# Peripheral.net
KiCad netlist of a schematic drawn in Altium Designer
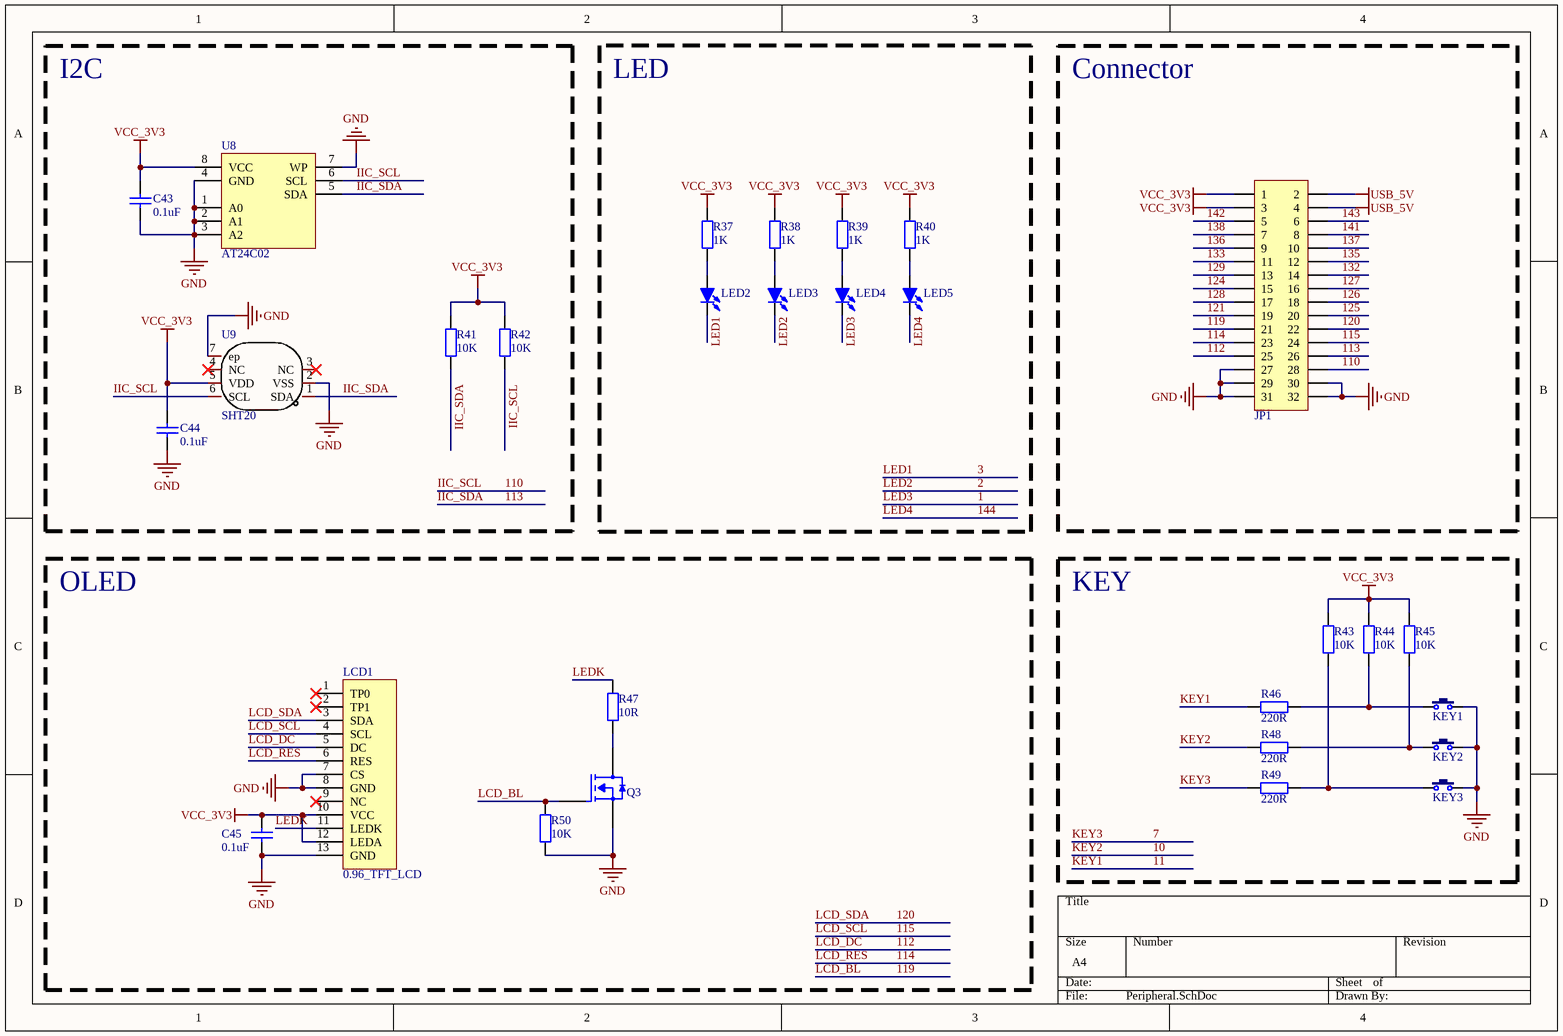
[diagram p0: Peripheral.SchDoc]

(export (version "E")
  (design (tool "Eeschema 10.0.6"))
  (components
    (comp (ref "C43")
      (value "0.1uF")
      (footprint "0402_C")
      (description "贴片电容")
      (libsource (lib "My_Devices") (part "0402_C"))
    )
    (comp (ref "C44")
      (value "0.1uF")
      (footprint "0402_C")
      (description "贴片电容")
      (libsource (lib "My_Devices") (part "0402_C"))
    )
    (comp (ref "C45")
      (value "0.1uF")
      (footprint "0402_C")
      (description "贴片电容")
      (libsource (lib "My_Devices") (part "0402_C"))
    )
    (comp (ref "JP1")
      (value "Header 2X11")
      (footprint "HDR2.54-LI-2x16P")
      (description "16*2P接插件")
      (fields (field (name "版权归属") "源创客"))
      (libsource (lib "My_Devices") (part "Header 16X2_2.54"))
    )
    (comp (ref "KEY1")
      (value "3x6x5")
      (footprint "SW")
      (description "3x6轻触开关")
      (fields (field (name "版权归属") "源创客"))
      (libsource (lib "My_Devices") (part "TSW 3x6"))
    )
    (comp (ref "KEY2")
      (value "3x6x5")
      (footprint "SW")
      (description "3x6轻触开关")
      (fields (field (name "版权归属") "源创客"))
      (libsource (lib "My_Devices") (part "TSW 3x6"))
    )
    (comp (ref "KEY3")
      (value "3x6x5")
      (footprint "SW")
      (description "3x6轻触开关")
      (fields (field (name "版权归属") "源创客"))
      (libsource (lib "My_Devices") (part "TSW 3x6"))
    )
    (comp (ref "LCD1")
      (value "0.96_TFT_LCD")
      (footprint "0.78_TFT_LCD")
      (libsource (lib "Schlib1") (part "0.96_TFT_LCD"))
    )
    (comp (ref "LED2")
      (value "红色")
      (footprint "LED 0603B")
      (description "贴片LED")
      (fields (field (name "版权归属") "源创客"))
      (libsource (lib "My_Devices") (part "0603_LED_B"))
    )
    (comp (ref "LED3")
      (value "红色")
      (footprint "LED 0603G")
      (description "贴片LED")
      (fields (field (name "版权归属") "源创客"))
      (libsource (lib "My_Devices") (part "0603_LED_G"))
    )
    (comp (ref "LED4")
      (value "红色")
      (footprint "LED 0603R")
      (description "贴片LED")
      (fields (field (name "版权归属") "源创客"))
      (libsource (lib "My_Devices") (part "0603_LED_R"))
    )
    (comp (ref "LED5")
      (value "红色")
      (footprint "LED 0603R")
      (description "贴片LED")
      (fields (field (name "版权归属") "源创客"))
      (libsource (lib "My_Devices") (part "0603_LED_R"))
    )
    (comp (ref "Q3")
      (value "AO3400A")
      (footprint "SOT23-3")
      (description "N-MOS")
      (libsource (lib "Schlib1") (part "AO3400A"))
    )
    (comp (ref "R37")
      (value "1K")
      (footprint "0402_R")
      (description "贴片电阻")
      (libsource (lib "My_Devices") (part "0402_R"))
    )
    (comp (ref "R38")
      (value "1K")
      (footprint "0402_R")
      (description "贴片电阻")
      (libsource (lib "My_Devices") (part "0402_R"))
    )
    (comp (ref "R39")
      (value "1K")
      (footprint "0402_R")
      (description "贴片电阻")
      (libsource (lib "My_Devices") (part "0402_R"))
    )
    (comp (ref "R40")
      (value "1K")
      (footprint "0402_R")
      (description "贴片电阻")
      (libsource (lib "My_Devices") (part "0402_R"))
    )
    (comp (ref "R41")
      (value "10K")
      (footprint "0402_R")
      (description "贴片电阻")
      (libsource (lib "") (part "0402_R_1"))
    )
    (comp (ref "R42")
      (value "10K")
      (footprint "0402_R")
      (description "贴片电阻")
      (libsource (lib "") (part "0402_R_1"))
    )
    (comp (ref "R43")
      (value "10K")
      (footprint "0402_R")
      (description "贴片电阻")
      (libsource (lib "") (part "0402_R_1"))
    )
    (comp (ref "R44")
      (value "10K")
      (footprint "0402_R")
      (description "贴片电阻")
      (libsource (lib "My_Devices") (part "0402_R"))
    )
    (comp (ref "R45")
      (value "10K")
      (footprint "0402_R")
      (description "贴片电阻")
      (libsource (lib "My_Devices") (part "0402_R"))
    )
    (comp (ref "R46")
      (value "220R")
      (footprint "0402_R")
      (description "贴片电阻")
      (libsource (lib "") (part "0402_R_1"))
    )
    (comp (ref "R47")
      (value "10R")
      (footprint "0402_R")
      (description "贴片电阻")
      (libsource (lib "My_Devices") (part "0402_R"))
    )
    (comp (ref "R48")
      (value "220R")
      (footprint "0402_R")
      (description "贴片电阻")
      (libsource (lib "") (part "0402_R_1"))
    )
    (comp (ref "R49")
      (value "220R")
      (footprint "0402_R")
      (description "贴片电阻")
      (libsource (lib "") (part "0402_R_1"))
    )
    (comp (ref "R50")
      (value "10K")
      (footprint "0402_R")
      (description "贴片电阻")
      (libsource (lib "My_Devices") (part "0402_R"))
    )
    (comp (ref "U8") (value "AT24C02") (footprint "SOP8_N") (libsource (lib "Schlib1") (part "AT24C02")))
    (comp (ref "U9")
      (value "SHT20")
      (footprint "DFN-6_L3.0-W3.0-P0.95-TR-EP")
      (description "I2C接口，数字式温湿度传感器，电压范围: 2.1至3.6 V")
      (fields (field (name "MANUFACTURER") "Sensirion(瑞士盛思锐)") (field (name "NAME") "SHT20"))
      (libsource (lib "Schlib1") (part "SHT20"))
    )
  )
  (nets
    (net (code "1") (name "/1") (class "Default")
      (node (ref "LED4") (pin "2") (pinfunction "K_2") (pintype "passive"))
    )
    (net (code "2") (name "/2") (class "Default")
      (node (ref "LED3") (pin "2") (pinfunction "K_2") (pintype "passive"))
    )
    (net (code "3") (name "/3") (class "Default")
      (node (ref "LED2") (pin "2") (pinfunction "K_2") (pintype "passive"))
    )
    (net (code "4") (name "/7") (class "Default")
      (node (ref "R49") (pin "2") (pinfunction "2_2") (pintype "passive"))
    )
    (net (code "5") (name "/10") (class "Default")
      (node (ref "R48") (pin "2") (pinfunction "2_2") (pintype "passive"))
    )
    (net (code "6") (name "/11") (class "Default")
      (node (ref "R46") (pin "2") (pinfunction "2_2") (pintype "passive"))
    )
    (net (code "7") (name "/110") (class "Default")
      (node (ref "JP1") (pin "28") (pinfunction "28_28") (pintype "passive"))
      (node (ref "R42") (pin "2") (pinfunction "2_2") (pintype "passive"))
      (node (ref "U8") (pin "6") (pinfunction "SCL_6") (pintype "passive"))
      (node (ref "U9") (pin "6") (pinfunction "SCL_6") (pintype "passive"))
    )
    (net (code "8") (name "/112") (class "Default")
      (node (ref "JP1") (pin "25") (pinfunction "25_25") (pintype "passive"))
      (node (ref "LCD1") (pin "5") (pinfunction "DC_5") (pintype "passive"))
    )
    (net (code "9") (name "/113") (class "Default")
      (node (ref "JP1") (pin "26") (pinfunction "26_26") (pintype "passive"))
      (node (ref "R41") (pin "2") (pinfunction "2_2") (pintype "passive"))
      (node (ref "U8") (pin "5") (pinfunction "SDA_5") (pintype "passive"))
      (node (ref "U9") (pin "1") (pinfunction "SDA_1") (pintype "passive"))
    )
    (net (code "10") (name "/114") (class "Default")
      (node (ref "JP1") (pin "23") (pinfunction "23_23") (pintype "passive"))
      (node (ref "LCD1") (pin "6") (pinfunction "RES_6") (pintype "passive"))
    )
    (net (code "11") (name "/115") (class "Default")
      (node (ref "JP1") (pin "24") (pinfunction "24_24") (pintype "passive"))
      (node (ref "LCD1") (pin "4") (pinfunction "SCL_4") (pintype "passive"))
    )
    (net (code "12") (name "/119") (class "Default")
      (node (ref "JP1") (pin "21") (pinfunction "21_21") (pintype "passive"))
      (node (ref "Q3") (pin "1") (pinfunction "G_1") (pintype "passive"))
      (node (ref "R50") (pin "2") (pinfunction "2_2") (pintype "passive"))
    )
    (net (code "13") (name "/120") (class "Default")
      (node (ref "JP1") (pin "22") (pinfunction "22_22") (pintype "passive"))
      (node (ref "LCD1") (pin "3") (pinfunction "SDA_3") (pintype "passive"))
    )
    (net (code "14") (name "/121") (class "Default")
      (node (ref "JP1") (pin "19") (pinfunction "19_19") (pintype "passive"))
    )
    (net (code "15") (name "/124") (class "Default")
      (node (ref "JP1") (pin "15") (pinfunction "15_15") (pintype "passive"))
    )
    (net (code "16") (name "/125") (class "Default")
      (node (ref "JP1") (pin "20") (pinfunction "20_20") (pintype "passive"))
    )
    (net (code "17") (name "/126") (class "Default")
      (node (ref "JP1") (pin "18") (pinfunction "18_18") (pintype "passive"))
    )
    (net (code "18") (name "/127") (class "Default")
      (node (ref "JP1") (pin "16") (pinfunction "16_16") (pintype "passive"))
    )
    (net (code "19") (name "/128") (class "Default")
      (node (ref "JP1") (pin "17") (pinfunction "17_17") (pintype "passive"))
    )
    (net (code "20") (name "/129") (class "Default")
      (node (ref "JP1") (pin "13") (pinfunction "13_13") (pintype "passive"))
    )
    (net (code "21") (name "/132") (class "Default")
      (node (ref "JP1") (pin "14") (pinfunction "14_14") (pintype "passive"))
    )
    (net (code "22") (name "/133") (class "Default")
      (node (ref "JP1") (pin "11") (pinfunction "11_11") (pintype "passive"))
    )
    (net (code "23") (name "/135") (class "Default")
      (node (ref "JP1") (pin "12") (pinfunction "12_12") (pintype "passive"))
    )
    (net (code "24") (name "/136") (class "Default")
      (node (ref "JP1") (pin "9") (pinfunction "9_9") (pintype "passive"))
    )
    (net (code "25") (name "/137") (class "Default")
      (node (ref "JP1") (pin "10") (pinfunction "10_10") (pintype "passive"))
    )
    (net (code "26") (name "/138") (class "Default")
      (node (ref "JP1") (pin "7") (pinfunction "7_7") (pintype "passive"))
    )
    (net (code "27") (name "/141") (class "Default")
      (node (ref "JP1") (pin "8") (pinfunction "8_8") (pintype "passive"))
    )
    (net (code "28") (name "/142") (class "Default")
      (node (ref "JP1") (pin "5") (pinfunction "5_5") (pintype "passive"))
    )
    (net (code "29") (name "/143") (class "Default")
      (node (ref "JP1") (pin "6") (pinfunction "6_6") (pintype "passive"))
    )
    (net (code "30") (name "/144") (class "Default")
      (node (ref "LED5") (pin "2") (pinfunction "K_2") (pintype "passive"))
    )
    (net (code "31") (name "/LEDK") (class "Default")
      (node (ref "LCD1") (pin "11") (pinfunction "LEDK_11") (pintype "passive"))
      (node (ref "R47") (pin "2") (pinfunction "2_2") (pintype "passive"))
    )
    (net (code "32") (name "GND") (class "Default")
      (node (ref "C43") (pin "1") (pinfunction "1_1") (pintype "passive"))
      (node (ref "C44") (pin "1") (pinfunction "1_1") (pintype "passive"))
      (node (ref "C45") (pin "1") (pinfunction "1_1") (pintype "passive"))
      (node (ref "JP1") (pin "27") (pinfunction "27_27") (pintype "passive"))
      (node (ref "JP1") (pin "29") (pinfunction "29_29") (pintype "passive"))
      (node (ref "JP1") (pin "30") (pinfunction "30_30") (pintype "passive"))
      (node (ref "JP1") (pin "31") (pinfunction "31_31") (pintype "passive"))
      (node (ref "JP1") (pin "32") (pinfunction "32_32") (pintype "passive"))
      (node (ref "KEY1") (pin "1") (pinfunction "1_1") (pintype "passive"))
      (node (ref "KEY2") (pin "1") (pinfunction "1_1") (pintype "passive"))
      (node (ref "KEY3") (pin "1") (pinfunction "1_1") (pintype "passive"))
      (node (ref "LCD1") (pin "13") (pinfunction "GND_13") (pintype "passive"))
      (node (ref "LCD1") (pin "7") (pinfunction "CS_7") (pintype "passive"))
      (node (ref "LCD1") (pin "8") (pinfunction "GND_8") (pintype "passive"))
      (node (ref "Q3") (pin "2") (pinfunction "S_2") (pintype "passive"))
      (node (ref "R50") (pin "1") (pinfunction "1_1") (pintype "passive"))
      (node (ref "U8") (pin "1") (pinfunction "A0_1") (pintype "passive"))
      (node (ref "U8") (pin "2") (pinfunction "A1_2") (pintype "passive"))
      (node (ref "U8") (pin "3") (pinfunction "A2_3") (pintype "passive"))
      (node (ref "U8") (pin "4") (pinfunction "GND_4") (pintype "passive"))
      (node (ref "U8") (pin "7") (pinfunction "WP_7") (pintype "passive"))
      (node (ref "U9") (pin "2") (pinfunction "VSS_2") (pintype "passive"))
      (node (ref "U9") (pin "7") (pinfunction "ep_7") (pintype "passive"))
    )
    (net (code "33") (name "Net-(KEY1-Pad2)") (class "Default")
      (node (ref "KEY1") (pin "2") (pinfunction "2_2") (pintype "passive"))
      (node (ref "R44") (pin "1") (pinfunction "1_1") (pintype "passive"))
      (node (ref "R46") (pin "1") (pinfunction "1_1") (pintype "passive"))
    )
    (net (code "34") (name "Net-(KEY2-Pad2)") (class "Default")
      (node (ref "KEY2") (pin "2") (pinfunction "2_2") (pintype "passive"))
      (node (ref "R45") (pin "1") (pinfunction "1_1") (pintype "passive"))
      (node (ref "R48") (pin "1") (pinfunction "1_1") (pintype "passive"))
    )
    (net (code "35") (name "Net-(KEY3-Pad2)") (class "Default")
      (node (ref "KEY3") (pin "2") (pinfunction "2_2") (pintype "passive"))
      (node (ref "R43") (pin "2") (pinfunction "2_2") (pintype "passive"))
      (node (ref "R49") (pin "1") (pinfunction "1_1") (pintype "passive"))
    )
    (net (code "36") (name "Net-(LED2-A)") (class "Default")
      (node (ref "LED2") (pin "1") (pinfunction "A_1") (pintype "passive"))
      (node (ref "R37") (pin "1") (pinfunction "1_1") (pintype "passive"))
    )
    (net (code "37") (name "Net-(LED3-A)") (class "Default")
      (node (ref "LED3") (pin "1") (pinfunction "A_1") (pintype "passive"))
      (node (ref "R38") (pin "1") (pinfunction "1_1") (pintype "passive"))
    )
    (net (code "38") (name "Net-(LED4-A)") (class "Default")
      (node (ref "LED4") (pin "1") (pinfunction "A_1") (pintype "passive"))
      (node (ref "R39") (pin "1") (pinfunction "1_1") (pintype "passive"))
    )
    (net (code "39") (name "Net-(LED5-A)") (class "Default")
      (node (ref "LED5") (pin "1") (pinfunction "A_1") (pintype "passive"))
      (node (ref "R40") (pin "1") (pinfunction "1_1") (pintype "passive"))
    )
    (net (code "40") (name "Net-(Q3-D)") (class "Default")
      (node (ref "Q3") (pin "3") (pinfunction "D_3") (pintype "passive"))
      (node (ref "R47") (pin "1") (pinfunction "1_1") (pintype "passive"))
    )
    (net (code "41") (name "USB_5V") (class "Default")
      (node (ref "JP1") (pin "2") (pinfunction "2_2") (pintype "passive"))
      (node (ref "JP1") (pin "4") (pinfunction "4_4") (pintype "passive"))
    )
    (net (code "42") (name "VCC_3V3") (class "Default")
      (node (ref "C43") (pin "2") (pinfunction "2_2") (pintype "passive"))
      (node (ref "C44") (pin "2") (pinfunction "2_2") (pintype "passive"))
      (node (ref "C45") (pin "2") (pinfunction "2_2") (pintype "passive"))
      (node (ref "JP1") (pin "1") (pinfunction "1_1") (pintype "passive"))
      (node (ref "JP1") (pin "3") (pinfunction "3_3") (pintype "passive"))
      (node (ref "LCD1") (pin "10") (pinfunction "VCC_10") (pintype "passive"))
      (node (ref "LCD1") (pin "12") (pinfunction "LEDA_12") (pintype "passive"))
      (node (ref "R37") (pin "2") (pinfunction "2_2") (pintype "passive"))
      (node (ref "R38") (pin "2") (pinfunction "2_2") (pintype "passive"))
      (node (ref "R39") (pin "2") (pinfunction "2_2") (pintype "passive"))
      (node (ref "R40") (pin "2") (pinfunction "2_2") (pintype "passive"))
      (node (ref "R41") (pin "1") (pinfunction "1_1") (pintype "passive"))
      (node (ref "R42") (pin "1") (pinfunction "1_1") (pintype "passive"))
      (node (ref "R43") (pin "1") (pinfunction "1_1") (pintype "passive"))
      (node (ref "R44") (pin "2") (pinfunction "2_2") (pintype "passive"))
      (node (ref "R45") (pin "2") (pinfunction "2_2") (pintype "passive"))
      (node (ref "U8") (pin "8") (pinfunction "VCC_8") (pintype "passive"))
      (node (ref "U9") (pin "5") (pinfunction "VDD_5") (pintype "passive"))
    )
    (net (code "43") (name "unconnected-(LCD1-NC-Pad9)") (class "Default")
      (node (ref "LCD1") (pin "9") (pinfunction "NC_9") (pintype "passive+no_connect"))
    )
    (net (code "44") (name "unconnected-(LCD1-TP0-Pad1)") (class "Default")
      (node (ref "LCD1") (pin "1") (pinfunction "TP0_1") (pintype "passive+no_connect"))
    )
    (net (code "45") (name "unconnected-(LCD1-TP1-Pad2)") (class "Default")
      (node (ref "LCD1") (pin "2") (pinfunction "TP1_2") (pintype "passive+no_connect"))
    )
    (net (code "46") (name "unconnected-(U9-NC-Pad3)") (class "Default")
      (node (ref "U9") (pin "3") (pinfunction "NC_3") (pintype "passive+no_connect"))
    )
    (net (code "47") (name "unconnected-(U9-NC-Pad4)") (class "Default")
      (node (ref "U9") (pin "4") (pinfunction "NC_4") (pintype "passive+no_connect"))
    )
  )
)
